# Option_LPDDR2-32_168_BGA134.net
KiCad netlist of a schematic drawn in Altium Designer
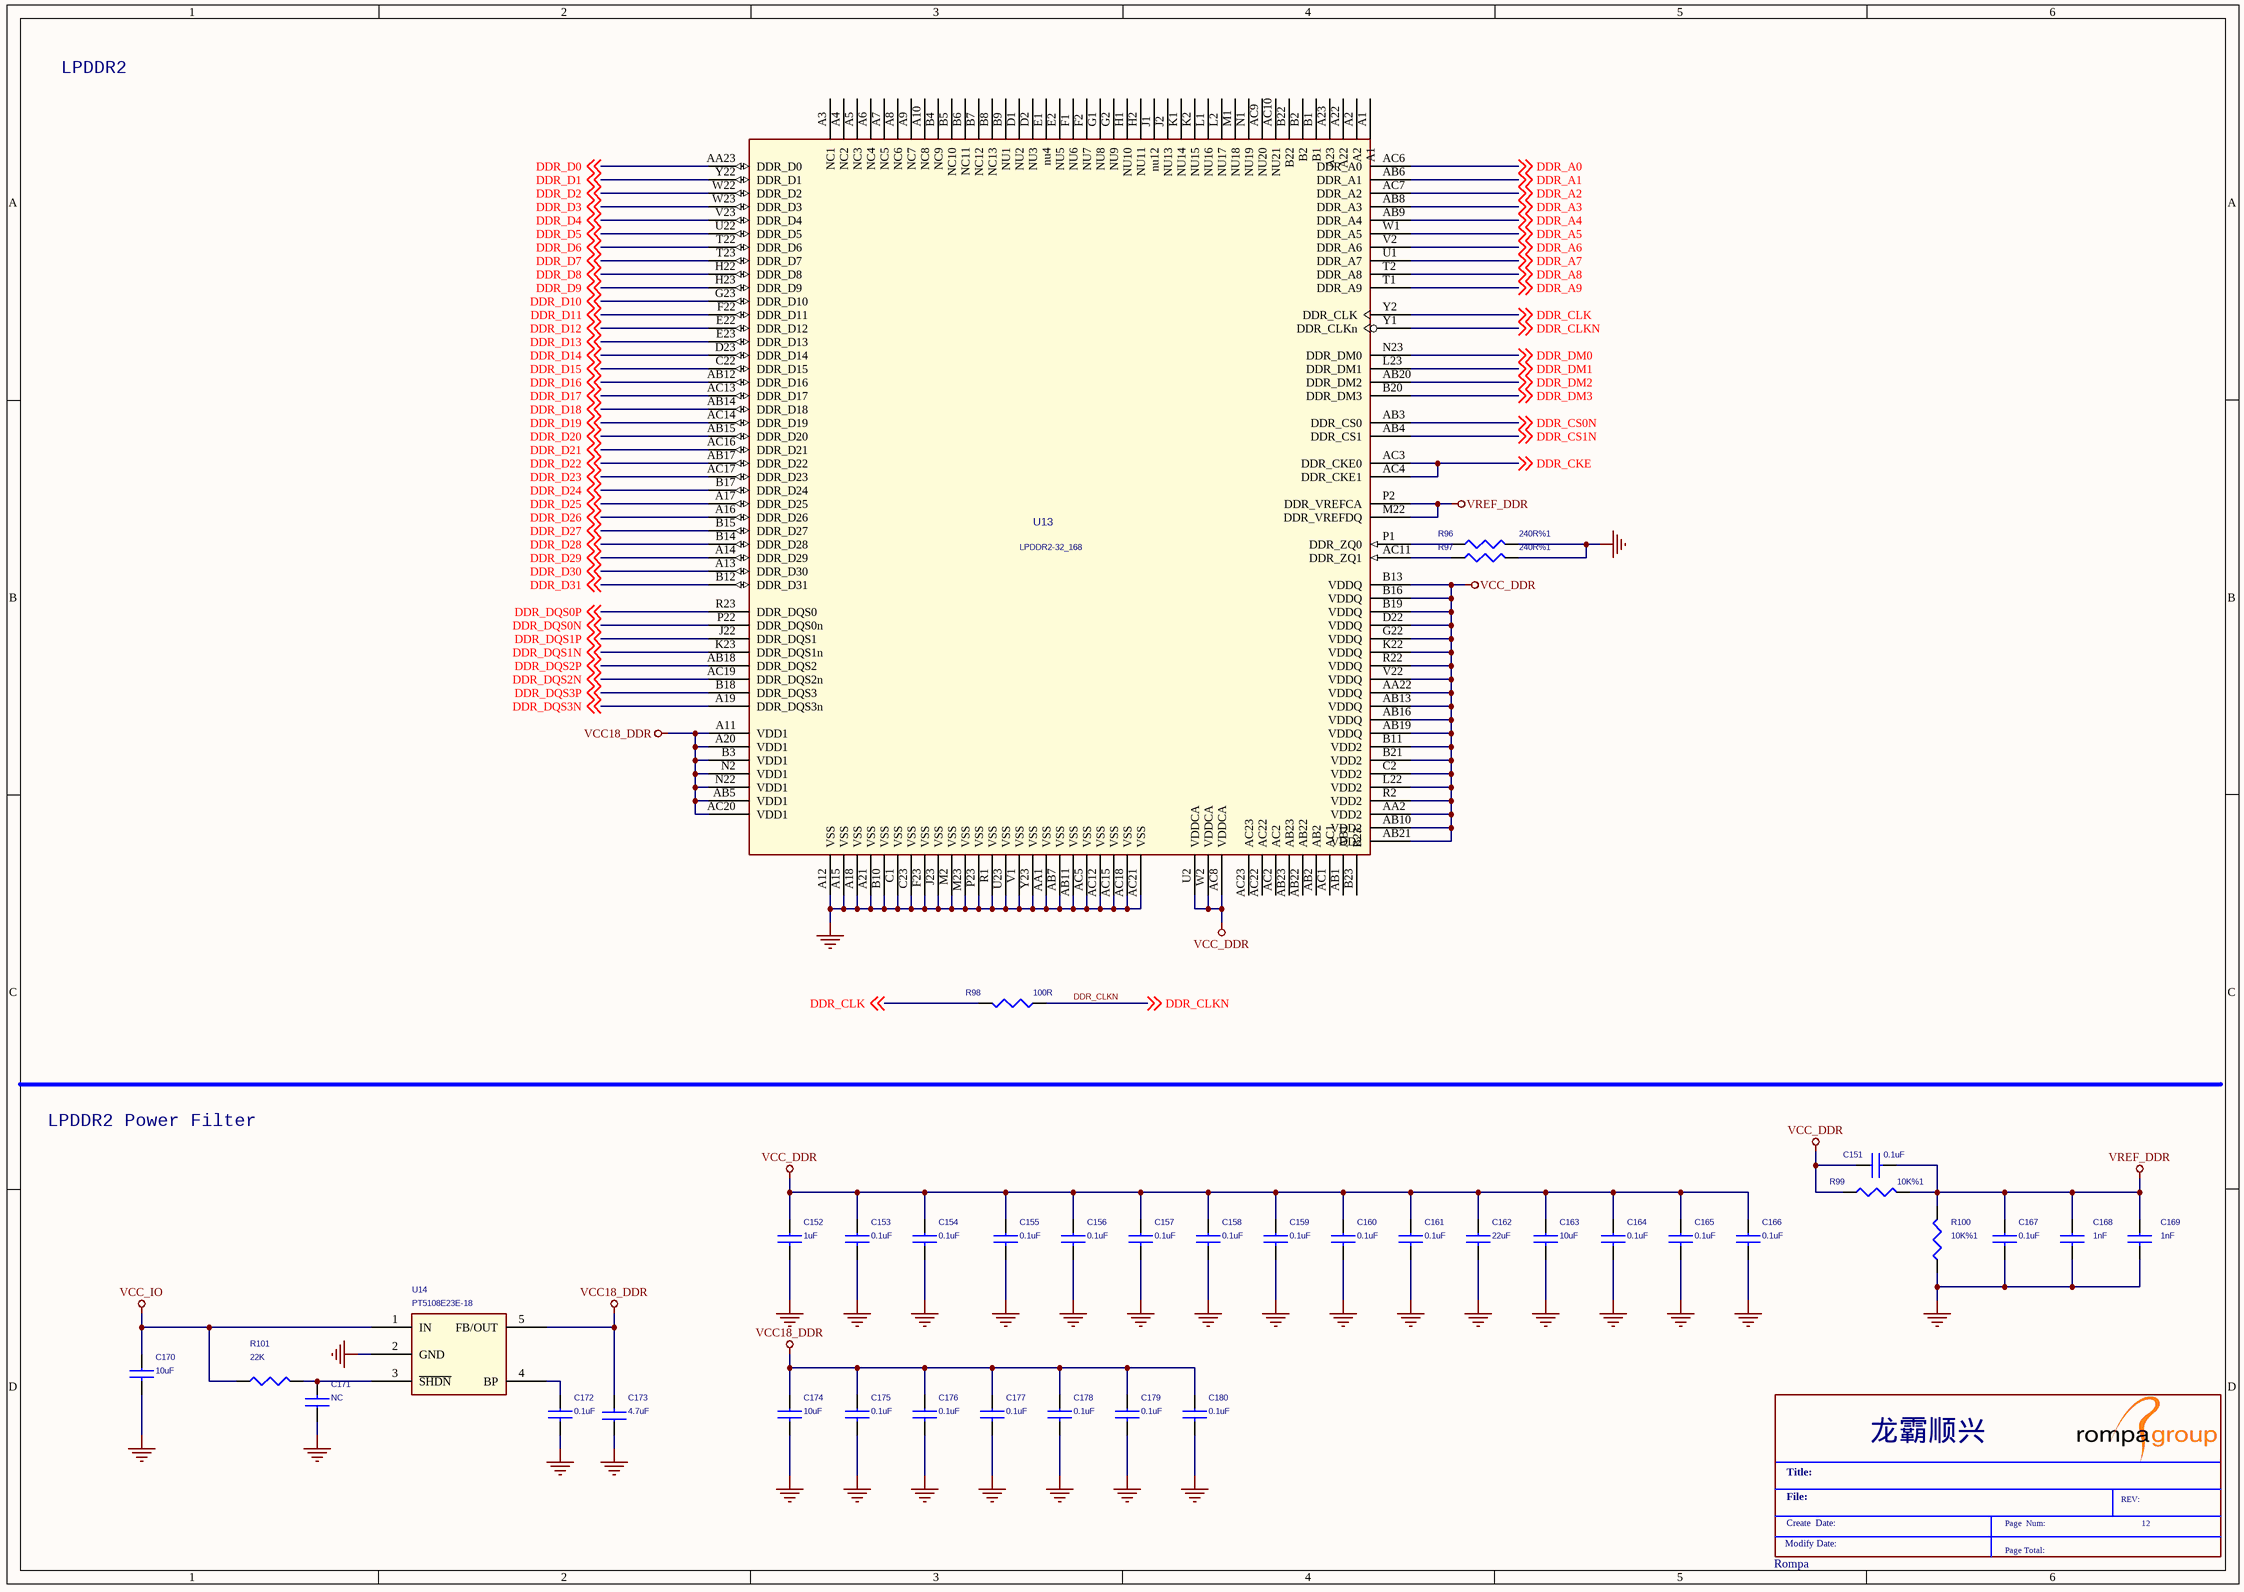
[diagram p0: Option_LPDDR2-32_168_BGA134.SchDoc]

(export (version "E")
  (design (tool "Eeschema 10.0.6"))
  (components
    (comp (ref "C151") (value "0.1uF") (footprint "C0402") (libsource (lib "*") (part "CAP NP_0")))
    (comp (ref "C152")
      (value "1uF")
      (footprint "C0402")
      (description "RoHS CHIP CAP 1uF +10/-10% X5R")
      (libsource (lib "*") (part "CAP NP"))
    )
    (comp (ref "C153")
      (value "0.1uF")
      (footprint "C0402")
      (description "RoHS CHIP CAP 1uF +10/-10% X5R")
      (libsource (lib "*") (part "CAP NP"))
    )
    (comp (ref "C154")
      (value "0.1uF")
      (footprint "C0402")
      (description "RoHS CHIP CAP 0.1uF +10/-10% X7R")
      (libsource (lib "*") (part "CAP NP"))
    )
    (comp (ref "C155")
      (value "0.1uF")
      (footprint "C0402")
      (description "RoHS CHIP CAP 0.1uF +10/-10% X7R")
      (libsource (lib "*") (part "CAP NP"))
    )
    (comp (ref "C156")
      (value "0.1uF")
      (footprint "C0402")
      (description "RoHS CHIP CAP 0.1uF +10/-10% X7R")
      (libsource (lib "*") (part "CAP NP"))
    )
    (comp (ref "C157")
      (value "0.1uF")
      (footprint "C0402")
      (description "RoHS CHIP CAP 0.1uF +10/-10% X7R")
      (libsource (lib "*") (part "CAP NP"))
    )
    (comp (ref "C158")
      (value "0.1uF")
      (footprint "C0402")
      (description "RoHS CHIP CAP 0.1uF +10/-10% X7R")
      (libsource (lib "*") (part "CAP NP"))
    )
    (comp (ref "C159")
      (value "0.1uF")
      (footprint "C0402")
      (description "RoHS CHIP CAP 0.1uF +10/-10% X7R")
      (libsource (lib "*") (part "CAP NP"))
    )
    (comp (ref "C160")
      (value "0.1uF")
      (footprint "C0402")
      (description "RoHS CHIP CAP 0.1uF +10/-10% X7R")
      (libsource (lib "*") (part "CAP NP"))
    )
    (comp (ref "C161")
      (value "0.1uF")
      (footprint "C0402")
      (description "RoHS CHIP CAP 0.1uF +10/-10% X7R")
      (libsource (lib "*") (part "CAP NP"))
    )
    (comp (ref "C162")
      (value "22uF")
      (footprint "C0402")
      (description "RoHS CHIP CAP 0.1uF +10/-10% X7R")
      (libsource (lib "*") (part "CAP NP"))
    )
    (comp (ref "C163")
      (value "10uF")
      (footprint "C0402")
      (description "RoHS CHIP CAP 0.1uF +10/-10% X7R")
      (libsource (lib "*") (part "CAP NP"))
    )
    (comp (ref "C164")
      (value "0.1uF")
      (footprint "C0402")
      (description "RoHS CHIP CAP 0.1uF +10/-10% X7R")
      (libsource (lib "*") (part "CAP NP"))
    )
    (comp (ref "C165")
      (value "0.1uF")
      (footprint "C0402")
      (description "RoHS CHIP CAP 0.1uF +10/-10% X7R")
      (libsource (lib "*") (part "CAP NP"))
    )
    (comp (ref "C166")
      (value "0.1uF")
      (footprint "C0402")
      (description "RoHS CHIP CAP 0.1uF +10/-10% X7R")
      (libsource (lib "*") (part "CAP NP"))
    )
    (comp (ref "C167") (value "0.1uF") (footprint "C0402") (libsource (lib "*") (part "CAP NP_0")))
    (comp (ref "C168") (value "1nF") (footprint "C0402") (libsource (lib "*") (part "CAP NP_0")))
    (comp (ref "C169") (value "1nF") (footprint "C0402") (libsource (lib "*") (part "CAP NP_0")))
    (comp (ref "C170")
      (value "10uF")
      (footprint "C0402")
      (description "CAP,MLCC,22uF,+/-10%,X5R,6.3V,SMD1206")
      (libsource (lib "*") (part "CAP NP"))
    )
    (comp (ref "C171") (value "NC") (footprint "C0402") (libsource (lib "*") (part "CAP NP")))
    (comp (ref "C172")
      (value "0.1uF")
      (footprint "C0402")
      (description "CAP,MLCC,100nF,+/-10%,X7R,6.3V,SMD0402")
      (libsource (lib "*") (part "CAP NP"))
    )
    (comp (ref "C173")
      (value "4.7uF")
      (footprint "C0402")
      (description "CAP,MLCC,10uF,+/-10%,X5R,6.3V,SMD0805")
      (libsource (lib "*") (part "CAP NP"))
    )
    (comp (ref "C174")
      (value "10uF")
      (footprint "C0402")
      (description "RoHS CHIP CAP 1uF +10/-10% X5R")
      (libsource (lib "*") (part "CAP NP"))
    )
    (comp (ref "C175")
      (value "0.1uF")
      (footprint "C0402")
      (description "RoHS CHIP CAP 0.1uF +10/-10% X7R")
      (libsource (lib "*") (part "CAP NP"))
    )
    (comp (ref "C176")
      (value "0.1uF")
      (footprint "C0402")
      (description "RoHS CHIP CAP 0.1uF +10/-10% X7R")
      (libsource (lib "*") (part "CAP NP"))
    )
    (comp (ref "C177")
      (value "0.1uF")
      (footprint "C0402")
      (description "RoHS CHIP CAP 0.1uF +10/-10% X7R")
      (libsource (lib "*") (part "CAP NP"))
    )
    (comp (ref "C178")
      (value "0.1uF")
      (footprint "C0402")
      (description "RoHS CHIP CAP 0.1uF +10/-10% X7R")
      (libsource (lib "*") (part "CAP NP"))
    )
    (comp (ref "C179")
      (value "0.1uF")
      (footprint "C0402")
      (description "RoHS CHIP CAP 0.1uF +10/-10% X7R")
      (libsource (lib "*") (part "CAP NP"))
    )
    (comp (ref "C180")
      (value "0.1uF")
      (footprint "C0402")
      (description "RoHS CHIP CAP 0.1uF +10/-10% X7R")
      (libsource (lib "*") (part "CAP NP"))
    )
    (comp (ref "R96")
      (value "240R%1")
      (footprint "R0402")
      (description "贴片电阻")
      (libsource (lib "*") (part "RESISTOR_0"))
    )
    (comp (ref "R97")
      (value "240R%1")
      (footprint "R0402")
      (description "贴片电阻")
      (libsource (lib "*") (part "RESISTOR_0"))
    )
    (comp (ref "R98")
      (value "100R")
      (footprint "R0402")
      (description "NC/ROHS CHIP RES 100R 1/16W 5%")
      (libsource (lib "*") (part "RESISTOR"))
    )
    (comp (ref "R99")
      (value "10K%1")
      (footprint "R0402")
      (description "贴片电阻")
      (libsource (lib "*") (part "RESISTOR_0"))
    )
    (comp (ref "R100")
      (value "10K%1")
      (footprint "R0402")
      (description "贴片电阻")
      (libsource (lib "*") (part "RESISTOR_0"))
    )
    (comp (ref "R101") (value "22K") (footprint "R0402") (libsource (lib "*") (part "RES 1B")))
    (comp (ref "U13") (value "LPDDR2-32_168") (footprint "BGA134") (libsource (lib "*") (part "LPDDR2-32_2")))
    (comp (ref "U14")
      (value "PT5108E23E-18")
      (footprint "SOT25")
      (description "LDO,PT5108E23E-18,VINmax=5.5V,Vout=1.8V,+/-2%,500mA,SOT-23-5")
      (libsource (lib "*") (part "DS8008_4"))
    )
  )
  (nets
    (net (code "1") (name "DDR_A0") (class "Default")
      (node (ref "U13") (pin "AC6") (pinfunction "DDR_A0_AC6") (pintype "passive"))
    )
    (net (code "2") (name "DDR_A1") (class "Default")
      (node (ref "U13") (pin "AB6") (pinfunction "DDR_A1_AB6") (pintype "passive"))
    )
    (net (code "3") (name "DDR_A2") (class "Default")
      (node (ref "U13") (pin "AC7") (pinfunction "DDR_A2_AC7") (pintype "passive"))
    )
    (net (code "4") (name "DDR_A3") (class "Default")
      (node (ref "U13") (pin "AB8") (pinfunction "DDR_A3_AB8") (pintype "passive"))
    )
    (net (code "5") (name "DDR_A4") (class "Default")
      (node (ref "U13") (pin "AB9") (pinfunction "DDR_A4_AB9") (pintype "passive"))
    )
    (net (code "6") (name "DDR_A5") (class "Default")
      (node (ref "U13") (pin "W1") (pinfunction "DDR_A5_W1") (pintype "passive"))
    )
    (net (code "7") (name "DDR_A6") (class "Default")
      (node (ref "U13") (pin "V2") (pinfunction "DDR_A6_V2") (pintype "passive"))
    )
    (net (code "8") (name "DDR_A7") (class "Default")
      (node (ref "U13") (pin "U1") (pinfunction "DDR_A7_U1") (pintype "passive"))
    )
    (net (code "9") (name "DDR_A8") (class "Default")
      (node (ref "U13") (pin "T2") (pinfunction "DDR_A8_T2") (pintype "passive"))
    )
    (net (code "10") (name "DDR_A9") (class "Default")
      (node (ref "U13") (pin "T1") (pinfunction "DDR_A9_T1") (pintype "passive"))
    )
    (net (code "11") (name "DDR_CKE") (class "Default")
      (node (ref "U13") (pin "AC3") (pinfunction "DDR_CKE0_AC3") (pintype "passive"))
      (node (ref "U13") (pin "AC4") (pinfunction "DDR_CKE1_AC4") (pintype "passive"))
    )
    (net (code "12") (name "DDR_CLK") (class "Default")
      (node (ref "R98") (pin "2") (pinfunction "2_2") (pintype "passive"))
      (node (ref "U13") (pin "Y2") (pinfunction "DDR_CLK_Y2") (pintype "passive"))
    )
    (net (code "13") (name "DDR_CLKN") (class "Default")
      (node (ref "R98") (pin "1") (pinfunction "1_1") (pintype "passive"))
      (node (ref "U13") (pin "Y1") (pinfunction "DDR_CLKn_Y1") (pintype "passive"))
    )
    (net (code "14") (name "DDR_CS0N") (class "Default")
      (node (ref "U13") (pin "AB3") (pinfunction "DDR_CS0_AB3") (pintype "passive"))
    )
    (net (code "15") (name "DDR_CS1N") (class "Default")
      (node (ref "U13") (pin "AB4") (pinfunction "DDR_CS1_AB4") (pintype "passive"))
    )
    (net (code "16") (name "DDR_D0") (class "Default")
      (node (ref "U13") (pin "AA23") (pinfunction "DDR_D0_AA23") (pintype "bidirectional"))
    )
    (net (code "17") (name "DDR_D1") (class "Default")
      (node (ref "U13") (pin "Y22") (pinfunction "DDR_D1_Y22") (pintype "bidirectional"))
    )
    (net (code "18") (name "DDR_D2") (class "Default")
      (node (ref "U13") (pin "W22") (pinfunction "DDR_D2_W22") (pintype "bidirectional"))
    )
    (net (code "19") (name "DDR_D3") (class "Default")
      (node (ref "U13") (pin "W23") (pinfunction "DDR_D3_W23") (pintype "bidirectional"))
    )
    (net (code "20") (name "DDR_D4") (class "Default")
      (node (ref "U13") (pin "V23") (pinfunction "DDR_D4_V23") (pintype "bidirectional"))
    )
    (net (code "21") (name "DDR_D5") (class "Default")
      (node (ref "U13") (pin "U22") (pinfunction "DDR_D5_U22") (pintype "bidirectional"))
    )
    (net (code "22") (name "DDR_D6") (class "Default")
      (node (ref "U13") (pin "T22") (pinfunction "DDR_D6_T22") (pintype "bidirectional"))
    )
    (net (code "23") (name "DDR_D7") (class "Default")
      (node (ref "U13") (pin "T23") (pinfunction "DDR_D7_T23") (pintype "bidirectional"))
    )
    (net (code "24") (name "DDR_D8") (class "Default")
      (node (ref "U13") (pin "H22") (pinfunction "DDR_D8_H22") (pintype "bidirectional"))
    )
    (net (code "25") (name "DDR_D9") (class "Default")
      (node (ref "U13") (pin "H23") (pinfunction "DDR_D9_H23") (pintype "bidirectional"))
    )
    (net (code "26") (name "DDR_D10") (class "Default")
      (node (ref "U13") (pin "G23") (pinfunction "DDR_D10_G23") (pintype "bidirectional"))
    )
    (net (code "27") (name "DDR_D11") (class "Default")
      (node (ref "U13") (pin "F22") (pinfunction "DDR_D11_F22") (pintype "bidirectional"))
    )
    (net (code "28") (name "DDR_D12") (class "Default")
      (node (ref "U13") (pin "E22") (pinfunction "DDR_D12_E22") (pintype "bidirectional"))
    )
    (net (code "29") (name "DDR_D13") (class "Default")
      (node (ref "U13") (pin "E23") (pinfunction "DDR_D13_E23") (pintype "bidirectional"))
    )
    (net (code "30") (name "DDR_D14") (class "Default")
      (node (ref "U13") (pin "D23") (pinfunction "DDR_D14_D23") (pintype "bidirectional"))
    )
    (net (code "31") (name "DDR_D15") (class "Default")
      (node (ref "U13") (pin "C22") (pinfunction "DDR_D15_C22") (pintype "bidirectional"))
    )
    (net (code "32") (name "DDR_D16") (class "Default")
      (node (ref "U13") (pin "AB12") (pinfunction "DDR_D16_AB12") (pintype "bidirectional"))
    )
    (net (code "33") (name "DDR_D17") (class "Default")
      (node (ref "U13") (pin "AC13") (pinfunction "DDR_D17_AC13") (pintype "bidirectional"))
    )
    (net (code "34") (name "DDR_D18") (class "Default")
      (node (ref "U13") (pin "AB14") (pinfunction "DDR_D18_AB14") (pintype "bidirectional"))
    )
    (net (code "35") (name "DDR_D19") (class "Default")
      (node (ref "U13") (pin "AC14") (pinfunction "DDR_D19_AC14") (pintype "bidirectional"))
    )
    (net (code "36") (name "DDR_D20") (class "Default")
      (node (ref "U13") (pin "AB15") (pinfunction "DDR_D20_AB15") (pintype "bidirectional"))
    )
    (net (code "37") (name "DDR_D21") (class "Default")
      (node (ref "U13") (pin "AC16") (pinfunction "DDR_D21_AC16") (pintype "bidirectional"))
    )
    (net (code "38") (name "DDR_D22") (class "Default")
      (node (ref "U13") (pin "AB17") (pinfunction "DDR_D22_AB17") (pintype "bidirectional"))
    )
    (net (code "39") (name "DDR_D23") (class "Default")
      (node (ref "U13") (pin "AC17") (pinfunction "DDR_D23_AC17") (pintype "bidirectional"))
    )
    (net (code "40") (name "DDR_D24") (class "Default")
      (node (ref "U13") (pin "B17") (pinfunction "DDR_D24_B17") (pintype "bidirectional"))
    )
    (net (code "41") (name "DDR_D25") (class "Default")
      (node (ref "U13") (pin "A17") (pinfunction "DDR_D25_A17") (pintype "bidirectional"))
    )
    (net (code "42") (name "DDR_D26") (class "Default")
      (node (ref "U13") (pin "A16") (pinfunction "DDR_D26_A16") (pintype "bidirectional"))
    )
    (net (code "43") (name "DDR_D27") (class "Default")
      (node (ref "U13") (pin "B15") (pinfunction "DDR_D27_B15") (pintype "bidirectional"))
    )
    (net (code "44") (name "DDR_D28") (class "Default")
      (node (ref "U13") (pin "B14") (pinfunction "DDR_D28_B14") (pintype "bidirectional"))
    )
    (net (code "45") (name "DDR_D29") (class "Default")
      (node (ref "U13") (pin "A14") (pinfunction "DDR_D29_A14") (pintype "bidirectional"))
    )
    (net (code "46") (name "DDR_D30") (class "Default")
      (node (ref "U13") (pin "A13") (pinfunction "DDR_D30_A13") (pintype "bidirectional"))
    )
    (net (code "47") (name "DDR_D31") (class "Default")
      (node (ref "U13") (pin "B12") (pinfunction "DDR_D31_B12") (pintype "bidirectional"))
    )
    (net (code "48") (name "DDR_DM0") (class "Default")
      (node (ref "U13") (pin "N23") (pinfunction "DDR_DM0_N23") (pintype "passive"))
    )
    (net (code "49") (name "DDR_DM1") (class "Default")
      (node (ref "U13") (pin "L23") (pinfunction "DDR_DM1_L23") (pintype "passive"))
    )
    (net (code "50") (name "DDR_DM2") (class "Default")
      (node (ref "U13") (pin "AB20") (pinfunction "DDR_DM2_AB20") (pintype "passive"))
    )
    (net (code "51") (name "DDR_DM3") (class "Default")
      (node (ref "U13") (pin "B20") (pinfunction "DDR_DM3_B20") (pintype "passive"))
    )
    (net (code "52") (name "DDR_DQS0N") (class "Default")
      (node (ref "U13") (pin "P22") (pinfunction "DDR_DQS0n_P22") (pintype "passive"))
    )
    (net (code "53") (name "DDR_DQS0P") (class "Default")
      (node (ref "U13") (pin "R23") (pinfunction "DDR_DQS0_R23") (pintype "passive"))
    )
    (net (code "54") (name "DDR_DQS1N") (class "Default")
      (node (ref "U13") (pin "K23") (pinfunction "DDR_DQS1n_K23") (pintype "passive"))
    )
    (net (code "55") (name "DDR_DQS1P") (class "Default")
      (node (ref "U13") (pin "J22") (pinfunction "DDR_DQS1_J22") (pintype "passive"))
    )
    (net (code "56") (name "DDR_DQS2N") (class "Default")
      (node (ref "U13") (pin "AC19") (pinfunction "DDR_DQS2n_AC19") (pintype "passive"))
    )
    (net (code "57") (name "DDR_DQS2P") (class "Default")
      (node (ref "U13") (pin "AB18") (pinfunction "DDR_DQS2_AB18") (pintype "passive"))
    )
    (net (code "58") (name "DDR_DQS3N") (class "Default")
      (node (ref "U13") (pin "A19") (pinfunction "DDR_DQS3n_A19") (pintype "passive"))
    )
    (net (code "59") (name "DDR_DQS3P") (class "Default")
      (node (ref "U13") (pin "B18") (pinfunction "DDR_DQS3_B18") (pintype "passive"))
    )
    (net (code "60") (name "GND") (class "Default")
      (node (ref "C152") (pin "2") (pinfunction "2_2") (pintype "passive"))
      (node (ref "C153") (pin "2") (pinfunction "2_2") (pintype "passive"))
      (node (ref "C154") (pin "2") (pinfunction "2_2") (pintype "passive"))
      (node (ref "C155") (pin "2") (pinfunction "2_2") (pintype "passive"))
      (node (ref "C156") (pin "2") (pinfunction "2_2") (pintype "passive"))
      (node (ref "C157") (pin "2") (pinfunction "2_2") (pintype "passive"))
      (node (ref "C158") (pin "2") (pinfunction "2_2") (pintype "passive"))
      (node (ref "C159") (pin "2") (pinfunction "2_2") (pintype "passive"))
      (node (ref "C160") (pin "2") (pinfunction "2_2") (pintype "passive"))
      (node (ref "C161") (pin "2") (pinfunction "2_2") (pintype "passive"))
      (node (ref "C162") (pin "2") (pinfunction "2_2") (pintype "passive"))
      (node (ref "C163") (pin "2") (pinfunction "2_2") (pintype "passive"))
      (node (ref "C164") (pin "2") (pinfunction "2_2") (pintype "passive"))
      (node (ref "C165") (pin "2") (pinfunction "2_2") (pintype "passive"))
      (node (ref "C166") (pin "2") (pinfunction "2_2") (pintype "passive"))
      (node (ref "C167") (pin "2") (pinfunction "2_2") (pintype "passive"))
      (node (ref "C168") (pin "2") (pinfunction "2_2") (pintype "passive"))
      (node (ref "C169") (pin "2") (pinfunction "2_2") (pintype "passive"))
      (node (ref "C170") (pin "2") (pinfunction "2_2") (pintype "passive"))
      (node (ref "C171") (pin "1") (pinfunction "1_1") (pintype "passive"))
      (node (ref "C172") (pin "2") (pinfunction "2_2") (pintype "passive"))
      (node (ref "C173") (pin "1") (pinfunction "1_1") (pintype "passive"))
      (node (ref "C174") (pin "2") (pinfunction "2_2") (pintype "passive"))
      (node (ref "C175") (pin "2") (pinfunction "2_2") (pintype "passive"))
      (node (ref "C176") (pin "2") (pinfunction "2_2") (pintype "passive"))
      (node (ref "C177") (pin "2") (pinfunction "2_2") (pintype "passive"))
      (node (ref "C178") (pin "2") (pinfunction "2_2") (pintype "passive"))
      (node (ref "C179") (pin "2") (pinfunction "2_2") (pintype "passive"))
      (node (ref "C180") (pin "2") (pinfunction "2_2") (pintype "passive"))
      (node (ref "R100") (pin "1") (pinfunction "1_1") (pintype "passive"))
      (node (ref "R96") (pin "2") (pinfunction "2_2") (pintype "passive"))
      (node (ref "R97") (pin "2") (pinfunction "2_2") (pintype "passive"))
      (node (ref "U13") (pin "A12") (pinfunction "VSS_A12") (pintype "power_in"))
      (node (ref "U13") (pin "A15") (pinfunction "VSS_A15") (pintype "power_in"))
      (node (ref "U13") (pin "A18") (pinfunction "VSS_A18") (pintype "power_in"))
      (node (ref "U13") (pin "A21") (pinfunction "VSS_A21") (pintype "power_in"))
      (node (ref "U13") (pin "AA1") (pinfunction "VSS_AA1") (pintype "power_in"))
      (node (ref "U13") (pin "AB11") (pinfunction "VSS_AB11") (pintype "power_in"))
      (node (ref "U13") (pin "AB7") (pinfunction "VSS_AB7") (pintype "power_in"))
      (node (ref "U13") (pin "AC12") (pinfunction "VSS_AC12") (pintype "power_in"))
      (node (ref "U13") (pin "AC15") (pinfunction "VSS_AC15") (pintype "power_in"))
      (node (ref "U13") (pin "AC18") (pinfunction "VSS_AC18") (pintype "power_in"))
      (node (ref "U13") (pin "AC21") (pinfunction "VSS_AC21") (pintype "power_in"))
      (node (ref "U13") (pin "AC5") (pinfunction "VSS_AC5") (pintype "power_in"))
      (node (ref "U13") (pin "B10") (pinfunction "VSS_B10") (pintype "power_in"))
      (node (ref "U13") (pin "C1") (pinfunction "VSS_C1") (pintype "power_in"))
      (node (ref "U13") (pin "C23") (pinfunction "VSS_C23") (pintype "power_in"))
      (node (ref "U13") (pin "F23") (pinfunction "VSS_F23") (pintype "power_in"))
      (node (ref "U13") (pin "J23") (pinfunction "VSS_J23") (pintype "power_in"))
      (node (ref "U13") (pin "M2") (pinfunction "VSS_M2") (pintype "power_in"))
      (node (ref "U13") (pin "M23") (pinfunction "VSS_M23") (pintype "power_in"))
      (node (ref "U13") (pin "P23") (pinfunction "VSS_P23") (pintype "power_in"))
      (node (ref "U13") (pin "R1") (pinfunction "VSS_R1") (pintype "power_in"))
      (node (ref "U13") (pin "U23") (pinfunction "VSS_U23") (pintype "power_in"))
      (node (ref "U13") (pin "V1") (pinfunction "VSS_V1") (pintype "power_in"))
      (node (ref "U13") (pin "Y23") (pinfunction "VSS_Y23") (pintype "power_in"))
      (node (ref "U14") (pin "2") (pinfunction "GND_2") (pintype "passive"))
    )
    (net (code "61") (name "Net-(U13-DDR_ZQ0)") (class "Default")
      (node (ref "R96") (pin "1") (pinfunction "1_1") (pintype "passive"))
      (node (ref "U13") (pin "P1") (pinfunction "DDR_ZQ0_P1") (pintype "input"))
    )
    (net (code "62") (name "Net-(U13-DDR_ZQ1)") (class "Default")
      (node (ref "R97") (pin "1") (pinfunction "1_1") (pintype "passive"))
      (node (ref "U13") (pin "AC11") (pinfunction "DDR_ZQ1_AC11") (pintype "input"))
    )
    (net (code "63") (name "Net-(U14-BP)") (class "Default")
      (node (ref "C172") (pin "1") (pinfunction "1_1") (pintype "passive"))
      (node (ref "U14") (pin "4") (pinfunction "BP_4") (pintype "passive"))
    )
    (net (code "64") (name "Net-(U14-~{SHDN})") (class "Default")
      (node (ref "C171") (pin "2") (pinfunction "2_2") (pintype "passive"))
      (node (ref "R101") (pin "2") (pinfunction "2_2") (pintype "passive"))
      (node (ref "U14") (pin "3") (pinfunction "~{SHDN}_3") (pintype "passive"))
    )
    (net (code "65") (name "VCC18_DDR") (class "Default")
      (node (ref "C173") (pin "2") (pinfunction "2_2") (pintype "passive"))
      (node (ref "C174") (pin "1") (pinfunction "1_1") (pintype "passive"))
      (node (ref "C175") (pin "1") (pinfunction "1_1") (pintype "passive"))
      (node (ref "C176") (pin "1") (pinfunction "1_1") (pintype "passive"))
      (node (ref "C177") (pin "1") (pinfunction "1_1") (pintype "passive"))
      (node (ref "C178") (pin "1") (pinfunction "1_1") (pintype "passive"))
      (node (ref "C179") (pin "1") (pinfunction "1_1") (pintype "passive"))
      (node (ref "C180") (pin "1") (pinfunction "1_1") (pintype "passive"))
      (node (ref "U13") (pin "A11") (pinfunction "VDD1_A11") (pintype "power_in"))
      (node (ref "U13") (pin "A20") (pinfunction "VDD1_A20") (pintype "power_in"))
      (node (ref "U13") (pin "AB5") (pinfunction "VDD1_AB5") (pintype "power_in"))
      (node (ref "U13") (pin "AC20") (pinfunction "VDD1_AC20") (pintype "power_in"))
      (node (ref "U13") (pin "B3") (pinfunction "VDD1_B3") (pintype "power_in"))
      (node (ref "U13") (pin "N2") (pinfunction "VDD1_N2") (pintype "power_in"))
      (node (ref "U13") (pin "N22") (pinfunction "VDD1_N22") (pintype "power_in"))
      (node (ref "U14") (pin "5") (pinfunction "FB/OUT_5") (pintype "passive"))
    )
    (net (code "66") (name "VCC_DDR") (class "Default")
      (node (ref "C151") (pin "1") (pinfunction "1_1") (pintype "passive"))
      (node (ref "C152") (pin "1") (pinfunction "1_1") (pintype "passive"))
      (node (ref "C153") (pin "1") (pinfunction "1_1") (pintype "passive"))
      (node (ref "C154") (pin "1") (pinfunction "1_1") (pintype "passive"))
      (node (ref "C155") (pin "1") (pinfunction "1_1") (pintype "passive"))
      (node (ref "C156") (pin "1") (pinfunction "1_1") (pintype "passive"))
      (node (ref "C157") (pin "1") (pinfunction "1_1") (pintype "passive"))
      (node (ref "C158") (pin "1") (pinfunction "1_1") (pintype "passive"))
      (node (ref "C159") (pin "1") (pinfunction "1_1") (pintype "passive"))
      (node (ref "C160") (pin "1") (pinfunction "1_1") (pintype "passive"))
      (node (ref "C161") (pin "1") (pinfunction "1_1") (pintype "passive"))
      (node (ref "C162") (pin "1") (pinfunction "1_1") (pintype "passive"))
      (node (ref "C163") (pin "1") (pinfunction "1_1") (pintype "passive"))
      (node (ref "C164") (pin "1") (pinfunction "1_1") (pintype "passive"))
      (node (ref "C165") (pin "1") (pinfunction "1_1") (pintype "passive"))
      (node (ref "C166") (pin "1") (pinfunction "1_1") (pintype "passive"))
      (node (ref "R99") (pin "1") (pinfunction "1_1") (pintype "passive"))
      (node (ref "U13") (pin "AA2") (pinfunction "VDD2_AA2") (pintype "power_in"))
      (node (ref "U13") (pin "AA22") (pinfunction "VDDQ_AA22") (pintype "power_in"))
      (node (ref "U13") (pin "AB10") (pinfunction "VDD2_AB10") (pintype "power_in"))
      (node (ref "U13") (pin "AB13") (pinfunction "VDDQ_AB13") (pintype "power_in"))
      (node (ref "U13") (pin "AB16") (pinfunction "VDDQ_AB16") (pintype "power_in"))
      (node (ref "U13") (pin "AB19") (pinfunction "VDDQ_AB19") (pintype "power_in"))
      (node (ref "U13") (pin "AB21") (pinfunction "VDD2_AB21") (pintype "power_in"))
      (node (ref "U13") (pin "AC8") (pinfunction "VDDCA_AC8") (pintype "power_in"))
      (node (ref "U13") (pin "B11") (pinfunction "VDD2_B11") (pintype "power_in"))
      (node (ref "U13") (pin "B13") (pinfunction "VDDQ_B13") (pintype "power_in"))
      (node (ref "U13") (pin "B16") (pinfunction "VDDQ_B16") (pintype "power_in"))
      (node (ref "U13") (pin "B19") (pinfunction "VDDQ_B19") (pintype "power_in"))
      (node (ref "U13") (pin "B21") (pinfunction "VDD2_B21") (pintype "power_in"))
      (node (ref "U13") (pin "C2") (pinfunction "VDD2_C2") (pintype "power_in"))
      (node (ref "U13") (pin "D22") (pinfunction "VDDQ_D22") (pintype "power_in"))
      (node (ref "U13") (pin "G22") (pinfunction "VDDQ_G22") (pintype "power_in"))
      (node (ref "U13") (pin "K22") (pinfunction "VDDQ_K22") (pintype "power_in"))
      (node (ref "U13") (pin "L22") (pinfunction "VDD2_L22") (pintype "power_in"))
      (node (ref "U13") (pin "R2") (pinfunction "VDD2_R2") (pintype "power_in"))
      (node (ref "U13") (pin "R22") (pinfunction "VDDQ_R22") (pintype "power_in"))
      (node (ref "U13") (pin "U2") (pinfunction "VDDCA_U2") (pintype "power_in"))
      (node (ref "U13") (pin "V22") (pinfunction "VDDQ_V22") (pintype "power_in"))
      (node (ref "U13") (pin "W2") (pinfunction "VDDCA_W2") (pintype "power_in"))
    )
    (net (code "67") (name "VCC_IO") (class "Default")
      (node (ref "C170") (pin "1") (pinfunction "1_1") (pintype "passive"))
      (node (ref "R101") (pin "1") (pinfunction "1_1") (pintype "passive"))
      (node (ref "U14") (pin "1") (pinfunction "IN_1") (pintype "passive"))
    )
    (net (code "68") (name "VREF_DDR") (class "Default")
      (node (ref "C151") (pin "2") (pinfunction "2_2") (pintype "passive"))
      (node (ref "C167") (pin "1") (pinfunction "1_1") (pintype "passive"))
      (node (ref "C168") (pin "1") (pinfunction "1_1") (pintype "passive"))
      (node (ref "C169") (pin "1") (pinfunction "1_1") (pintype "passive"))
      (node (ref "R100") (pin "2") (pinfunction "2_2") (pintype "passive"))
      (node (ref "R99") (pin "2") (pinfunction "2_2") (pintype "passive"))
      (node (ref "U13") (pin "M22") (pinfunction "DDR_VREFDQ_M22") (pintype "power_in"))
      (node (ref "U13") (pin "P2") (pinfunction "DDR_VREFCA_P2") (pintype "passive"))
    )
    (net (code "69") (name "unconnected-(U13-NC1-PadA3)") (class "Default")
      (node (ref "U13") (pin "A3") (pinfunction "NC1_A3") (pintype "passive"))
    )
    (net (code "70") (name "unconnected-(U13-NC2-PadA4)") (class "Default")
      (node (ref "U13") (pin "A4") (pinfunction "NC2_A4") (pintype "passive"))
    )
    (net (code "71") (name "unconnected-(U13-NC3-PadA5)") (class "Default")
      (node (ref "U13") (pin "A5") (pinfunction "NC3_A5") (pintype "passive"))
    )
    (net (code "72") (name "unconnected-(U13-NC4-PadA6)") (class "Default")
      (node (ref "U13") (pin "A6") (pinfunction "NC4_A6") (pintype "passive"))
    )
    (net (code "73") (name "unconnected-(U13-NC5-PadA7)") (class "Default")
      (node (ref "U13") (pin "A7") (pinfunction "NC5_A7") (pintype "passive"))
    )
    (net (code "74") (name "unconnected-(U13-NC6-PadA8)") (class "Default")
      (node (ref "U13") (pin "A8") (pinfunction "NC6_A8") (pintype "passive"))
    )
    (net (code "75") (name "unconnected-(U13-NC7-PadA9)") (class "Default")
      (node (ref "U13") (pin "A9") (pinfunction "NC7_A9") (pintype "passive"))
    )
    (net (code "76") (name "unconnected-(U13-NC8-PadA10)") (class "Default")
      (node (ref "U13") (pin "A10") (pinfunction "NC8_A10") (pintype "passive"))
    )
    (net (code "77") (name "unconnected-(U13-NC9-PadB4)") (class "Default")
      (node (ref "U13") (pin "B4") (pinfunction "NC9_B4") (pintype "passive"))
    )
    (net (code "78") (name "unconnected-(U13-NC10-PadB5)") (class "Default")
      (node (ref "U13") (pin "B5") (pinfunction "NC10_B5") (pintype "passive"))
    )
    (net (code "79") (name "unconnected-(U13-NC11-PadB6)") (class "Default")
      (node (ref "U13") (pin "B6") (pinfunction "NC11_B6") (pintype "passive"))
    )
    (net (code "80") (name "unconnected-(U13-NC12-PadB7)") (class "Default")
      (node (ref "U13") (pin "B7") (pinfunction "NC12_B7") (pintype "passive"))
    )
    (net (code "81") (name "unconnected-(U13-NC13-PadB8)") (class "Default")
      (node (ref "U13") (pin "B8") (pinfunction "NC13_B8") (pintype "passive"))
    )
    (net (code "82") (name "unconnected-(U13-NU1-PadB9)") (class "Default")
      (node (ref "U13") (pin "B9") (pinfunction "NU1_B9") (pintype "passive"))
    )
    (net (code "83") (name "unconnected-(U13-NU2-PadD1)") (class "Default")
      (node (ref "U13") (pin "D1") (pinfunction "NU2_D1") (pintype "passive"))
    )
    (net (code "84") (name "unconnected-(U13-NU3-PadD2)") (class "Default")
      (node (ref "U13") (pin "D2") (pinfunction "NU3_D2") (pintype "passive"))
    )
    (net (code "85") (name "unconnected-(U13-NU5-PadE2)") (class "Default")
      (node (ref "U13") (pin "E2") (pinfunction "NU5_E2") (pintype "passive"))
    )
    (net (code "86") (name "unconnected-(U13-NU6-PadF1)") (class "Default")
      (node (ref "U13") (pin "F1") (pinfunction "NU6_F1") (pintype "passive"))
    )
    (net (code "87") (name "unconnected-(U13-NU7-PadF2)") (class "Default")
      (node (ref "U13") (pin "F2") (pinfunction "NU7_F2") (pintype "passive"))
    )
    (net (code "88") (name "unconnected-(U13-NU8-PadG1)") (class "Default")
      (node (ref "U13") (pin "G1") (pinfunction "NU8_G1") (pintype "passive"))
    )
    (net (code "89") (name "unconnected-(U13-NU9-PadG2)") (class "Default")
      (node (ref "U13") (pin "G2") (pinfunction "NU9_G2") (pintype "passive"))
    )
    (net (code "90") (name "unconnected-(U13-NU10-PadH1)") (class "Default")
      (node (ref "U13") (pin "H1") (pinfunction "NU10_H1") (pintype "passive"))
    )
    (net (code "91") (name "unconnected-(U13-NU11-PadH2)") (class "Default")
      (node (ref "U13") (pin "H2") (pinfunction "NU11_H2") (pintype "passive"))
    )
    (net (code "92") (name "unconnected-(U13-NU13-PadJ2)") (class "Default")
      (node (ref "U13") (pin "J2") (pinfunction "NU13_J2") (pintype "passive"))
    )
    (net (code "93") (name "unconnected-(U13-NU14-PadK1)") (class "Default")
      (node (ref "U13") (pin "K1") (pinfunction "NU14_K1") (pintype "passive"))
    )
    (net (code "94") (name "unconnected-(U13-NU15-PadK2)") (class "Default")
      (node (ref "U13") (pin "K2") (pinfunction "NU15_K2") (pintype "passive"))
    )
    (net (code "95") (name "unconnected-(U13-NU16-PadL1)") (class "Default")
      (node (ref "U13") (pin "L1") (pinfunction "NU16_L1") (pintype "passive"))
    )
    (net (code "96") (name "unconnected-(U13-NU17-PadL2)") (class "Default")
      (node (ref "U13") (pin "L2") (pinfunction "NU17_L2") (pintype "passive"))
    )
    (net (code "97") (name "unconnected-(U13-NU18-PadM1)") (class "Default")
      (node (ref "U13") (pin "M1") (pinfunction "NU18_M1") (pintype "passive"))
    )
    (net (code "98") (name "unconnected-(U13-NU19-PadN1)") (class "Default")
      (node (ref "U13") (pin "N1") (pinfunction "NU19_N1") (pintype "passive"))
    )
    (net (code "99") (name "unconnected-(U13-NU20-PadAC9)") (class "Default")
      (node (ref "U13") (pin "AC9") (pinfunction "NU20_AC9") (pintype "passive"))
    )
    (net (code "100") (name "unconnected-(U13-NU21-PadAC10)") (class "Default")
      (node (ref "U13") (pin "AC10") (pinfunction "NU21_AC10") (pintype "passive"))
    )
    (net (code "101") (name "unconnected-(U13-PadA1)") (class "Default")
      (node (ref "U13") (pin "A1") (pinfunction "A1_A1") (pintype "passive"))
    )
    (net (code "102") (name "unconnected-(U13-PadA2)") (class "Default")
      (node (ref "U13") (pin "A2") (pinfunction "A2_A2") (pintype "passive"))
    )
    (net (code "103") (name "unconnected-(U13-PadA22)") (class "Default")
      (node (ref "U13") (pin "A22") (pinfunction "A22_A22") (pintype "passive"))
    )
    (net (code "104") (name "unconnected-(U13-PadA23)") (class "Default")
      (node (ref "U13") (pin "A23") (pinfunction "A23_A23") (pintype "passive"))
    )
    (net (code "105") (name "unconnected-(U13-PadAB1)") (class "Default")
      (node (ref "U13") (pin "AB1") (pinfunction "AB1_AB1") (pintype "power_in"))
    )
    (net (code "106") (name "unconnected-(U13-PadAB2)") (class "Default")
      (node (ref "U13") (pin "AB2") (pinfunction "AB2_AB2") (pintype "power_in"))
    )
    (net (code "107") (name "unconnected-(U13-PadAB22)") (class "Default")
      (node (ref "U13") (pin "AB22") (pinfunction "AB22_AB22") (pintype "power_in"))
    )
    (net (code "108") (name "unconnected-(U13-PadAB23)") (class "Default")
      (node (ref "U13") (pin "AB23") (pinfunction "AB23_AB23") (pintype "power_in"))
    )
    (net (code "109") (name "unconnected-(U13-PadAC1)") (class "Default")
      (node (ref "U13") (pin "AC1") (pinfunction "AC1_AC1") (pintype "power_in"))
    )
    (net (code "110") (name "unconnected-(U13-PadAC2)") (class "Default")
      (node (ref "U13") (pin "AC2") (pinfunction "AC2_AC2") (pintype "power_in"))
    )
    (net (code "111") (name "unconnected-(U13-PadAC22)") (class "Default")
      (node (ref "U13") (pin "AC22") (pinfunction "AC22_AC22") (pintype "power_in"))
    )
    (net (code "112") (name "unconnected-(U13-PadAC23)") (class "Default")
      (node (ref "U13") (pin "AC23") (pinfunction "AC23_AC23") (pintype "power_in"))
    )
    (net (code "113") (name "unconnected-(U13-PadB1)") (class "Default")
      (node (ref "U13") (pin "B1") (pinfunction "B1_B1") (pintype "passive"))
    )
    (net (code "114") (name "unconnected-(U13-PadB2)") (class "Default")
      (node (ref "U13") (pin "B2") (pinfunction "B2_B2") (pintype "passive"))
    )
    (net (code "115") (name "unconnected-(U13-PadB22)") (class "Default")
      (node (ref "U13") (pin "B22") (pinfunction "B22_B22") (pintype "passive"))
    )
    (net (code "116") (name "unconnected-(U13-PadB23)") (class "Default")
      (node (ref "U13") (pin "B23") (pinfunction "B23_B23") (pintype "power_in"))
    )
    (net (code "117") (name "unconnected-(U13-nu4-PadE1)") (class "Default")
      (node (ref "U13") (pin "E1") (pinfunction "nu4_E1") (pintype "passive"))
    )
    (net (code "118") (name "unconnected-(U13-nu12-PadJ1)") (class "Default")
      (node (ref "U13") (pin "J1") (pinfunction "nu12_J1") (pintype "passive"))
    )
  )
)
